# 4_LEDS_SEGMENT.net
KiCad netlist of a schematic drawn in Altium Designer
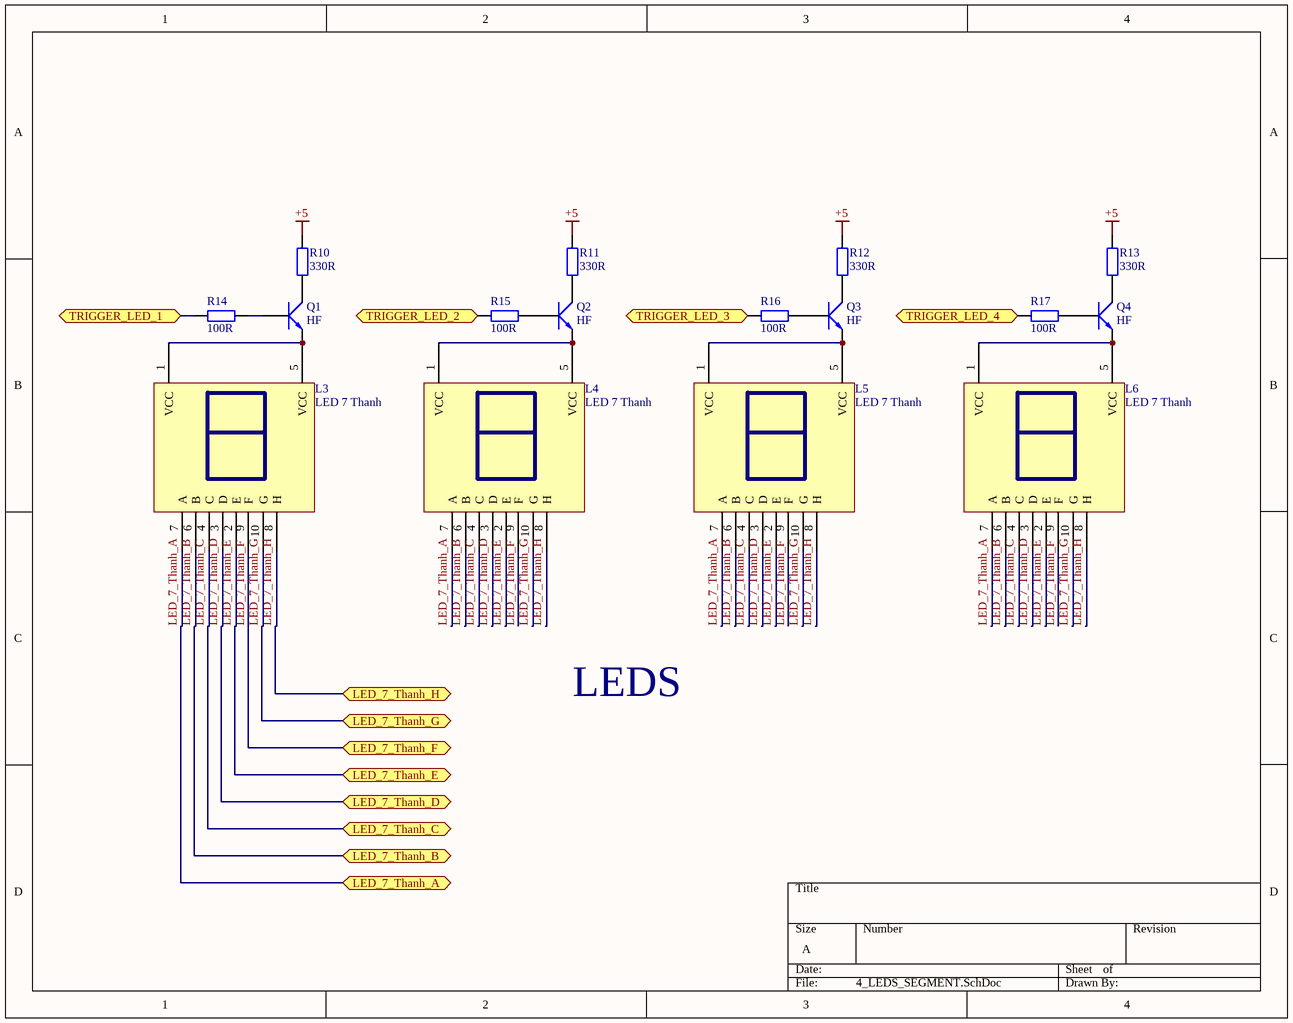
[diagram p0: 4_LEDS_SEGMENT.SchDoc]

(export (version "E")
  (design (tool "Eeschema 10.0.6"))
  (components
    (comp (ref "L3")
      (value "LED 7 Thanh")
      (footprint "LED7SEG_2.3inch")
      (description "Dán")
      (libsource (lib "Altium_Lib_by_KhueNguyenCreator") (part "LED 7x1 2.3inch Anot"))
    )
    (comp (ref "L4")
      (value "LED 7 Thanh")
      (footprint "LED7SEG_2.3inch")
      (description "Dán")
      (libsource (lib "Altium_Lib_by_KhueNguyenCreator") (part "LED 7x1 2.3inch Anot"))
    )
    (comp (ref "L5")
      (value "LED 7 Thanh")
      (footprint "LED7SEG_2.3inch")
      (description "Dán")
      (libsource (lib "Altium_Lib_by_KhueNguyenCreator") (part "LED 7x1 2.3inch Anot"))
    )
    (comp (ref "L6")
      (value "LED 7 Thanh")
      (footprint "LED7SEG_2.3inch")
      (description "Dán")
      (libsource (lib "Altium_Lib_by_KhueNguyenCreator") (part "LED 7x1 2.3inch Anot"))
    )
    (comp (ref "Q1")
      (value "HF")
      (footprint "SOT23")
      (description "NPN transistor")
      (libsource (lib "Altium_Lib_by_KhueNguyenCreator") (part "C1815 HF SMD"))
    )
    (comp (ref "Q2")
      (value "HF")
      (footprint "SOT23")
      (description "NPN transistor")
      (libsource (lib "Altium_Lib_by_KhueNguyenCreator") (part "C1815 HF SMD"))
    )
    (comp (ref "Q3")
      (value "HF")
      (footprint "SOT23")
      (description "NPN transistor")
      (libsource (lib "Altium_Lib_by_KhueNguyenCreator") (part "C1815 HF SMD"))
    )
    (comp (ref "Q4")
      (value "HF")
      (footprint "SOT23")
      (description "NPN transistor")
      (libsource (lib "Altium_Lib_by_KhueNguyenCreator") (part "C1815 HF SMD"))
    )
    (comp (ref "R10")
      (value "330R")
      (footprint "tro smd 0603")
      (description "Dán")
      (libsource (lib "Altium_Lib_by_KhueNguyenCreator") (part "Tro 0603 5% 330R"))
    )
    (comp (ref "R11")
      (value "330R")
      (footprint "tro smd 0603")
      (description "Dán")
      (libsource (lib "Altium_Lib_by_KhueNguyenCreator") (part "Tro 0603 5% 330R"))
    )
    (comp (ref "R12")
      (value "330R")
      (footprint "tro smd 0603")
      (description "Dán")
      (libsource (lib "Altium_Lib_by_KhueNguyenCreator") (part "Tro 0603 5% 330R"))
    )
    (comp (ref "R13")
      (value "330R")
      (footprint "tro smd 0603")
      (description "Dán")
      (libsource (lib "Altium_Lib_by_KhueNguyenCreator") (part "Tro 0603 5% 330R"))
    )
    (comp (ref "R14")
      (value "100R")
      (footprint "tro smd 0603")
      (description "Dán")
      (libsource (lib "Altium_Lib_by_KhueNguyenCreator") (part "Tro 0603 5% 100R"))
    )
    (comp (ref "R15")
      (value "100R")
      (footprint "tro smd 0603")
      (description "Dán")
      (libsource (lib "Altium_Lib_by_KhueNguyenCreator") (part "Tro 0603 5% 100R"))
    )
    (comp (ref "R16")
      (value "100R")
      (footprint "tro smd 0603")
      (description "Dán")
      (libsource (lib "Altium_Lib_by_KhueNguyenCreator") (part "Tro 0603 5% 100R"))
    )
    (comp (ref "R17")
      (value "100R")
      (footprint "tro smd 0603")
      (description "Dán")
      (libsource (lib "Altium_Lib_by_KhueNguyenCreator") (part "Tro 0603 5% 100R"))
    )
  )
  (nets
    (net (code "1") (name "+5") (class "Default")
      (node (ref "R10") (pin "2") (pinfunction "2_2") (pintype "passive"))
      (node (ref "R11") (pin "2") (pinfunction "2_2") (pintype "passive"))
      (node (ref "R12") (pin "2") (pinfunction "2_2") (pintype "passive"))
      (node (ref "R13") (pin "2") (pinfunction "2_2") (pintype "passive"))
    )
    (net (code "2") (name "/LED_7_Thanh_A") (class "Default")
      (node (ref "L3") (pin "7") (pinfunction "A_7") (pintype "passive"))
      (node (ref "L4") (pin "7") (pinfunction "A_7") (pintype "passive"))
      (node (ref "L5") (pin "7") (pinfunction "A_7") (pintype "passive"))
      (node (ref "L6") (pin "7") (pinfunction "A_7") (pintype "passive"))
    )
    (net (code "3") (name "/LED_7_Thanh_B") (class "Default")
      (node (ref "L3") (pin "6") (pinfunction "B_6") (pintype "passive"))
      (node (ref "L4") (pin "6") (pinfunction "B_6") (pintype "passive"))
      (node (ref "L5") (pin "6") (pinfunction "B_6") (pintype "passive"))
      (node (ref "L6") (pin "6") (pinfunction "B_6") (pintype "passive"))
    )
    (net (code "4") (name "/LED_7_Thanh_C") (class "Default")
      (node (ref "L3") (pin "4") (pinfunction "C_4") (pintype "passive"))
      (node (ref "L4") (pin "4") (pinfunction "C_4") (pintype "passive"))
      (node (ref "L5") (pin "4") (pinfunction "C_4") (pintype "passive"))
      (node (ref "L6") (pin "4") (pinfunction "C_4") (pintype "passive"))
    )
    (net (code "5") (name "/LED_7_Thanh_D") (class "Default")
      (node (ref "L3") (pin "3") (pinfunction "D_3") (pintype "passive"))
      (node (ref "L4") (pin "3") (pinfunction "D_3") (pintype "passive"))
      (node (ref "L5") (pin "3") (pinfunction "D_3") (pintype "passive"))
      (node (ref "L6") (pin "3") (pinfunction "D_3") (pintype "passive"))
    )
    (net (code "6") (name "/LED_7_Thanh_E") (class "Default")
      (node (ref "L3") (pin "2") (pinfunction "E_2") (pintype "passive"))
      (node (ref "L4") (pin "2") (pinfunction "E_2") (pintype "passive"))
      (node (ref "L5") (pin "2") (pinfunction "E_2") (pintype "passive"))
      (node (ref "L6") (pin "2") (pinfunction "E_2") (pintype "passive"))
    )
    (net (code "7") (name "/LED_7_Thanh_F") (class "Default")
      (node (ref "L3") (pin "9") (pinfunction "F_9") (pintype "passive"))
      (node (ref "L4") (pin "9") (pinfunction "F_9") (pintype "passive"))
      (node (ref "L5") (pin "9") (pinfunction "F_9") (pintype "passive"))
      (node (ref "L6") (pin "9") (pinfunction "F_9") (pintype "passive"))
    )
    (net (code "8") (name "/LED_7_Thanh_G") (class "Default")
      (node (ref "L3") (pin "10") (pinfunction "G_10") (pintype "passive"))
      (node (ref "L4") (pin "10") (pinfunction "G_10") (pintype "passive"))
      (node (ref "L5") (pin "10") (pinfunction "G_10") (pintype "passive"))
      (node (ref "L6") (pin "10") (pinfunction "G_10") (pintype "passive"))
    )
    (net (code "9") (name "/LED_7_Thanh_H") (class "Default")
      (node (ref "L3") (pin "8") (pinfunction "H_8") (pintype "passive"))
      (node (ref "L4") (pin "8") (pinfunction "H_8") (pintype "passive"))
      (node (ref "L5") (pin "8") (pinfunction "H_8") (pintype "passive"))
      (node (ref "L6") (pin "8") (pinfunction "H_8") (pintype "passive"))
    )
    (net (code "10") (name "/TRIGGER_LED_1") (class "Default")
      (node (ref "R14") (pin "1") (pinfunction "1_1") (pintype "passive"))
    )
    (net (code "11") (name "/TRIGGER_LED_2") (class "Default")
      (node (ref "R15") (pin "1") (pinfunction "1_1") (pintype "passive"))
    )
    (net (code "12") (name "/TRIGGER_LED_3") (class "Default")
      (node (ref "R16") (pin "1") (pinfunction "1_1") (pintype "passive"))
    )
    (net (code "13") (name "/TRIGGER_LED_4") (class "Default")
      (node (ref "R17") (pin "1") (pinfunction "1_1") (pintype "passive"))
    )
    (net (code "14") (name "Net-(Q1-B)") (class "Default")
      (node (ref "Q1") (pin "1") (pinfunction "B_1") (pintype "passive"))
      (node (ref "R14") (pin "2") (pinfunction "2_2") (pintype "passive"))
    )
    (net (code "15") (name "Net-(Q1-C)") (class "Default")
      (node (ref "Q1") (pin "3") (pinfunction "C_3") (pintype "passive"))
      (node (ref "R10") (pin "1") (pinfunction "1_1") (pintype "passive"))
    )
    (net (code "16") (name "Net-(Q1-E)") (class "Default")
      (node (ref "L3") (pin "1") (pinfunction "VCC_1") (pintype "passive"))
      (node (ref "L3") (pin "5") (pinfunction "VCC_5") (pintype "passive"))
      (node (ref "Q1") (pin "2") (pinfunction "E_2") (pintype "passive"))
    )
    (net (code "17") (name "Net-(Q2-B)") (class "Default")
      (node (ref "Q2") (pin "1") (pinfunction "B_1") (pintype "passive"))
      (node (ref "R15") (pin "2") (pinfunction "2_2") (pintype "passive"))
    )
    (net (code "18") (name "Net-(Q2-C)") (class "Default")
      (node (ref "Q2") (pin "3") (pinfunction "C_3") (pintype "passive"))
      (node (ref "R11") (pin "1") (pinfunction "1_1") (pintype "passive"))
    )
    (net (code "19") (name "Net-(Q2-E)") (class "Default")
      (node (ref "L4") (pin "1") (pinfunction "VCC_1") (pintype "passive"))
      (node (ref "L4") (pin "5") (pinfunction "VCC_5") (pintype "passive"))
      (node (ref "Q2") (pin "2") (pinfunction "E_2") (pintype "passive"))
    )
    (net (code "20") (name "Net-(Q3-B)") (class "Default")
      (node (ref "Q3") (pin "1") (pinfunction "B_1") (pintype "passive"))
      (node (ref "R16") (pin "2") (pinfunction "2_2") (pintype "passive"))
    )
    (net (code "21") (name "Net-(Q3-C)") (class "Default")
      (node (ref "Q3") (pin "3") (pinfunction "C_3") (pintype "passive"))
      (node (ref "R12") (pin "1") (pinfunction "1_1") (pintype "passive"))
    )
    (net (code "22") (name "Net-(Q3-E)") (class "Default")
      (node (ref "L5") (pin "1") (pinfunction "VCC_1") (pintype "passive"))
      (node (ref "L5") (pin "5") (pinfunction "VCC_5") (pintype "passive"))
      (node (ref "Q3") (pin "2") (pinfunction "E_2") (pintype "passive"))
    )
    (net (code "23") (name "Net-(Q4-B)") (class "Default")
      (node (ref "Q4") (pin "1") (pinfunction "B_1") (pintype "passive"))
      (node (ref "R17") (pin "2") (pinfunction "2_2") (pintype "passive"))
    )
    (net (code "24") (name "Net-(Q4-C)") (class "Default")
      (node (ref "Q4") (pin "3") (pinfunction "C_3") (pintype "passive"))
      (node (ref "R13") (pin "1") (pinfunction "1_1") (pintype "passive"))
    )
    (net (code "25") (name "Net-(Q4-E)") (class "Default")
      (node (ref "L6") (pin "1") (pinfunction "VCC_1") (pintype "passive"))
      (node (ref "L6") (pin "5") (pinfunction "VCC_5") (pintype "passive"))
      (node (ref "Q4") (pin "2") (pinfunction "E_2") (pintype "passive"))
    )
  )
)
